# Sheet3.net
KiCad netlist of a schematic drawn in Altium Designer
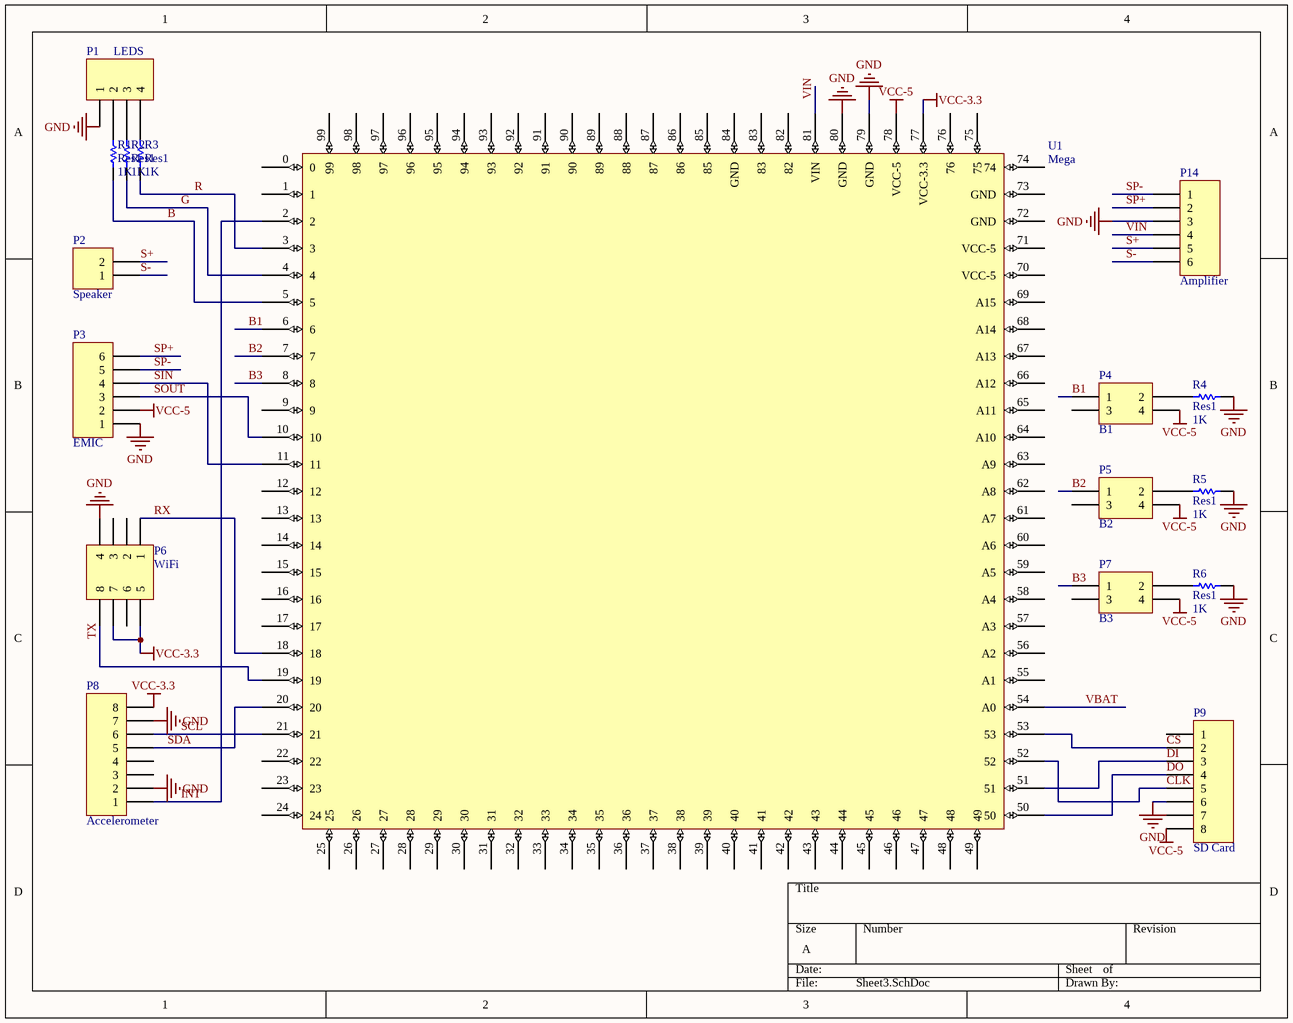
[diagram p0: Sheet3.SchDoc]

(export (version "E")
  (design (tool "Eeschema 10.0.6"))
  (components
    (comp (ref "P1")
      (value "LEDS")
      (footprint "HDR1X4")
      (description "Header, 4-Pin")
      (fields (field (name "PUBLISHER") "Altium Limited"))
      (libsource (lib "Miscellaneous Connectors") (part "Header 4"))
    )
    (comp (ref "P2")
      (value "Speaker")
      (footprint "HDR1X2")
      (description "Header, 2-Pin")
      (fields (field (name "PUBLISHER") "Altium Limited"))
      (libsource (lib "Miscellaneous Connectors") (part "Header 2"))
    )
    (comp (ref "P3")
      (value "EMIC")
      (footprint "EMIC")
      (description "Header, 6-Pin")
      (fields (field (name "PUBLISHER") "Altium Limited"))
      (libsource (lib "Miscellaneous Connectors") (part "Header 6"))
    )
    (comp (ref "P4")
      (value "B1")
      (footprint "HDR2X2")
      (description "Header, 2-Pin, Dual row")
      (fields (field (name "PUBLISHER") "Altium Limited"))
      (libsource (lib "Miscellaneous Connectors") (part "Header 2X2"))
    )
    (comp (ref "P5")
      (value "B2")
      (footprint "HDR2X2")
      (description "Header, 2-Pin, Dual row")
      (fields (field (name "PUBLISHER") "Altium Limited"))
      (libsource (lib "Miscellaneous Connectors") (part "Header 2X2"))
    )
    (comp (ref "P6")
      (value "WiFi")
      (footprint "WiFi")
      (description "Header, 4-Pin, Dual row")
      (fields (field (name "PUBLISHER") "Altium Limited"))
      (libsource (lib "Miscellaneous Connectors") (part "Header 4X2A"))
    )
    (comp (ref "P7")
      (value "B3")
      (footprint "HDR2X2")
      (description "Header, 2-Pin, Dual row")
      (fields (field (name "PUBLISHER") "Altium Limited"))
      (libsource (lib "Miscellaneous Connectors") (part "Header 2X2"))
    )
    (comp (ref "P8")
      (value "Accelerometer")
      (footprint "Acceelrometer")
      (description "Header, 8-Pin")
      (fields (field (name "PUBLISHER") "Altium Limited"))
      (libsource (lib "") (part "Header 8_1"))
    )
    (comp (ref "P9")
      (value "SD Card")
      (footprint "SD Card")
      (description "Header, 8-Pin")
      (fields (field (name "PUBLISHER") "Altium Limited"))
      (libsource (lib "Miscellaneous Connectors") (part "Header 8"))
    )
    (comp (ref "P14")
      (value "Amplifier")
      (footprint "HDR1X6")
      (description "Header, 6-Pin")
      (fields (field (name "PUBLISHER") "Altium Limited"))
      (libsource (lib "") (part "Header 6_1"))
    )
    (comp (ref "R1")
      (value "Res1")
      (footprint "14-1210")
      (description "Resistor")
      (fields (field (name "ALTIUM_VALUE") "1K") (field (name "PUBLISHER") "Altium Limited"))
      (libsource (lib "Miscellaneous Devices") (part "Res1"))
    )
    (comp (ref "R2")
      (value "Res1")
      (footprint "14-1210")
      (description "Resistor")
      (fields (field (name "ALTIUM_VALUE") "1K") (field (name "PUBLISHER") "Altium Limited"))
      (libsource (lib "Miscellaneous Devices") (part "Res1"))
    )
    (comp (ref "R3")
      (value "Res1")
      (footprint "14-1210")
      (description "Resistor")
      (fields (field (name "ALTIUM_VALUE") "1K") (field (name "PUBLISHER") "Altium Limited"))
      (libsource (lib "Miscellaneous Devices") (part "Res1"))
    )
    (comp (ref "R4")
      (value "Res1")
      (footprint "14-1210")
      (description "Resistor")
      (fields (field (name "ALTIUM_VALUE") "1K") (field (name "PUBLISHER") "Altium Limited"))
      (libsource (lib "Miscellaneous Devices") (part "Res1"))
    )
    (comp (ref "R5")
      (value "Res1")
      (footprint "14-1210")
      (description "Resistor")
      (fields (field (name "ALTIUM_VALUE") "1K") (field (name "PUBLISHER") "Altium Limited"))
      (libsource (lib "Miscellaneous Devices") (part "Res1"))
    )
    (comp (ref "R6")
      (value "Res1")
      (footprint "14-1210")
      (description "Resistor")
      (fields (field (name "ALTIUM_VALUE") "1K") (field (name "PUBLISHER") "Altium Limited"))
      (libsource (lib "Miscellaneous Devices") (part "Res1"))
    )
    (comp (ref "U1")
      (value "Mega")
      (footprint "Mega")
      (description "MEGA")
      (libsource (lib "Schlib1") (part "Mega"))
    )
  )
  (nets
    (net (code "1") (name "/B") (class "Default")
      (node (ref "R1") (pin "1") (pinfunction "1_1") (pintype "passive"))
      (node (ref "U1") (pin "5") (pinfunction "5_5") (pintype "bidirectional"))
    )
    (net (code "2") (name "/B1") (class "Default")
      (node (ref "P4") (pin "1") (pinfunction "1_1") (pintype "passive"))
      (node (ref "U1") (pin "6") (pinfunction "6_6") (pintype "bidirectional"))
    )
    (net (code "3") (name "/B2") (class "Default")
      (node (ref "P5") (pin "1") (pinfunction "1_1") (pintype "passive"))
      (node (ref "U1") (pin "7") (pinfunction "7_7") (pintype "bidirectional"))
    )
    (net (code "4") (name "/B3") (class "Default")
      (node (ref "P7") (pin "1") (pinfunction "1_1") (pintype "passive"))
      (node (ref "U1") (pin "8") (pinfunction "8_8") (pintype "bidirectional"))
    )
    (net (code "5") (name "/CLK") (class "Default")
      (node (ref "P9") (pin "5") (pinfunction "5_5") (pintype "passive"))
      (node (ref "U1") (pin "52") (pinfunction "52_52") (pintype "bidirectional"))
    )
    (net (code "6") (name "/CS") (class "Default")
      (node (ref "P9") (pin "2") (pinfunction "2_2") (pintype "passive"))
      (node (ref "U1") (pin "53") (pinfunction "53_53") (pintype "bidirectional"))
    )
    (net (code "7") (name "/DI") (class "Default")
      (node (ref "P9") (pin "3") (pinfunction "3_3") (pintype "passive"))
      (node (ref "U1") (pin "51") (pinfunction "51_51") (pintype "bidirectional"))
    )
    (net (code "8") (name "/DO") (class "Default")
      (node (ref "P9") (pin "4") (pinfunction "4_4") (pintype "passive"))
      (node (ref "U1") (pin "50") (pinfunction "50_50") (pintype "bidirectional"))
    )
    (net (code "9") (name "/G") (class "Default")
      (node (ref "R2") (pin "1") (pinfunction "1_1") (pintype "passive"))
      (node (ref "U1") (pin "4") (pinfunction "4_4") (pintype "bidirectional"))
    )
    (net (code "10") (name "/INT") (class "Default")
      (node (ref "P8") (pin "1") (pinfunction "1_1") (pintype "passive"))
      (node (ref "U1") (pin "2") (pinfunction "2_2") (pintype "bidirectional"))
    )
    (net (code "11") (name "/R") (class "Default")
      (node (ref "R3") (pin "1") (pinfunction "1_1") (pintype "passive"))
      (node (ref "U1") (pin "3") (pinfunction "3_3") (pintype "bidirectional"))
    )
    (net (code "12") (name "/RX") (class "Default")
      (node (ref "P6") (pin "1") (pinfunction "1_1") (pintype "passive"))
      (node (ref "U1") (pin "18") (pinfunction "18_18") (pintype "bidirectional"))
    )
    (net (code "13") (name "/S+") (class "Default")
      (node (ref "P14") (pin "5") (pinfunction "5_5") (pintype "passive"))
      (node (ref "P2") (pin "2") (pinfunction "2_2") (pintype "passive"))
    )
    (net (code "14") (name "/S-") (class "Default")
      (node (ref "P14") (pin "6") (pinfunction "6_6") (pintype "passive"))
      (node (ref "P2") (pin "1") (pinfunction "1_1") (pintype "passive"))
    )
    (net (code "15") (name "/SCL") (class "Default")
      (node (ref "P8") (pin "6") (pinfunction "6_6") (pintype "passive"))
      (node (ref "U1") (pin "21") (pinfunction "21_21") (pintype "bidirectional"))
    )
    (net (code "16") (name "/SDA") (class "Default")
      (node (ref "P8") (pin "5") (pinfunction "5_5") (pintype "passive"))
      (node (ref "U1") (pin "20") (pinfunction "20_20") (pintype "bidirectional"))
    )
    (net (code "17") (name "/SIN") (class "Default")
      (node (ref "P3") (pin "4") (pinfunction "4_4") (pintype "passive"))
      (node (ref "U1") (pin "11") (pinfunction "11_11") (pintype "bidirectional"))
    )
    (net (code "18") (name "/SOUT") (class "Default")
      (node (ref "P3") (pin "3") (pinfunction "3_3") (pintype "passive"))
      (node (ref "U1") (pin "10") (pinfunction "10_10") (pintype "bidirectional"))
    )
    (net (code "19") (name "/SP+") (class "Default")
      (node (ref "P14") (pin "2") (pinfunction "2_2") (pintype "passive"))
      (node (ref "P3") (pin "6") (pinfunction "6_6") (pintype "passive"))
    )
    (net (code "20") (name "/SP-") (class "Default")
      (node (ref "P14") (pin "1") (pinfunction "1_1") (pintype "passive"))
      (node (ref "P3") (pin "5") (pinfunction "5_5") (pintype "passive"))
    )
    (net (code "21") (name "/TX") (class "Default")
      (node (ref "P6") (pin "8") (pinfunction "8_8") (pintype "passive"))
      (node (ref "U1") (pin "19") (pinfunction "19_19") (pintype "bidirectional"))
    )
    (net (code "22") (name "/VBAT") (class "Default")
      (node (ref "U1") (pin "54") (pinfunction "A0_54") (pintype "bidirectional"))
    )
    (net (code "23") (name "/VIN") (class "Default")
      (node (ref "P14") (pin "4") (pinfunction "4_4") (pintype "passive"))
      (node (ref "U1") (pin "81") (pinfunction "VIN_81") (pintype "bidirectional"))
    )
    (net (code "24") (name "GND") (class "Default")
      (node (ref "P1") (pin "1") (pinfunction "1_1") (pintype "passive"))
      (node (ref "P14") (pin "3") (pinfunction "3_3") (pintype "passive"))
      (node (ref "P3") (pin "1") (pinfunction "1_1") (pintype "passive"))
      (node (ref "P6") (pin "4") (pinfunction "4_4") (pintype "passive"))
      (node (ref "P8") (pin "2") (pinfunction "2_2") (pintype "passive"))
      (node (ref "P8") (pin "7") (pinfunction "7_7") (pintype "passive"))
      (node (ref "P9") (pin "6") (pinfunction "6_6") (pintype "passive"))
      (node (ref "R4") (pin "2") (pinfunction "2_2") (pintype "passive"))
      (node (ref "R5") (pin "2") (pinfunction "2_2") (pintype "passive"))
      (node (ref "R6") (pin "2") (pinfunction "2_2") (pintype "passive"))
      (node (ref "U1") (pin "79") (pinfunction "GND_79") (pintype "bidirectional"))
      (node (ref "U1") (pin "80") (pinfunction "GND_80") (pintype "bidirectional"))
    )
    (net (code "25") (name "Net-(P1-Pad2)") (class "Default")
      (node (ref "P1") (pin "2") (pinfunction "2_2") (pintype "passive"))
      (node (ref "R1") (pin "2") (pinfunction "2_2") (pintype "passive"))
    )
    (net (code "26") (name "Net-(P1-Pad3)") (class "Default")
      (node (ref "P1") (pin "3") (pinfunction "3_3") (pintype "passive"))
      (node (ref "R2") (pin "2") (pinfunction "2_2") (pintype "passive"))
    )
    (net (code "27") (name "Net-(P1-Pad4)") (class "Default")
      (node (ref "P1") (pin "4") (pinfunction "4_4") (pintype "passive"))
      (node (ref "R3") (pin "2") (pinfunction "2_2") (pintype "passive"))
    )
    (net (code "28") (name "Net-(P4-Pad2)") (class "Default")
      (node (ref "P4") (pin "2") (pinfunction "2_2") (pintype "passive"))
      (node (ref "R4") (pin "1") (pinfunction "1_1") (pintype "passive"))
    )
    (net (code "29") (name "Net-(P5-Pad2)") (class "Default")
      (node (ref "P5") (pin "2") (pinfunction "2_2") (pintype "passive"))
      (node (ref "R5") (pin "1") (pinfunction "1_1") (pintype "passive"))
    )
    (net (code "30") (name "Net-(P7-Pad2)") (class "Default")
      (node (ref "P7") (pin "2") (pinfunction "2_2") (pintype "passive"))
      (node (ref "R6") (pin "1") (pinfunction "1_1") (pintype "passive"))
    )
    (net (code "31") (name "VCC-3.3") (class "Default")
      (node (ref "P6") (pin "5") (pinfunction "5_5") (pintype "passive"))
      (node (ref "P6") (pin "7") (pinfunction "7_7") (pintype "passive"))
      (node (ref "P8") (pin "8") (pinfunction "8_8") (pintype "passive"))
      (node (ref "U1") (pin "77") (pinfunction "VCC-3.3_77") (pintype "bidirectional"))
    )
    (net (code "32") (name "VCC-5") (class "Default")
      (node (ref "P3") (pin "2") (pinfunction "2_2") (pintype "passive"))
      (node (ref "P4") (pin "4") (pinfunction "4_4") (pintype "passive"))
      (node (ref "P5") (pin "4") (pinfunction "4_4") (pintype "passive"))
      (node (ref "P7") (pin "4") (pinfunction "4_4") (pintype "passive"))
      (node (ref "P9") (pin "8") (pinfunction "8_8") (pintype "passive"))
      (node (ref "U1") (pin "78") (pinfunction "VCC-5_78") (pintype "bidirectional"))
    )
    (net (code "33") (name "unconnected-(P4-Pad3)") (class "Default")
      (node (ref "P4") (pin "3") (pinfunction "3_3") (pintype "passive"))
    )
    (net (code "34") (name "unconnected-(P5-Pad3)") (class "Default")
      (node (ref "P5") (pin "3") (pinfunction "3_3") (pintype "passive"))
    )
    (net (code "35") (name "unconnected-(P6-Pad2)") (class "Default")
      (node (ref "P6") (pin "2") (pinfunction "2_2") (pintype "passive"))
    )
    (net (code "36") (name "unconnected-(P6-Pad3)") (class "Default")
      (node (ref "P6") (pin "3") (pinfunction "3_3") (pintype "passive"))
    )
    (net (code "37") (name "unconnected-(P6-Pad6)") (class "Default")
      (node (ref "P6") (pin "6") (pinfunction "6_6") (pintype "passive"))
    )
    (net (code "38") (name "unconnected-(P7-Pad3)") (class "Default")
      (node (ref "P7") (pin "3") (pinfunction "3_3") (pintype "passive"))
    )
    (net (code "39") (name "unconnected-(P8-Pad3)") (class "Default")
      (node (ref "P8") (pin "3") (pinfunction "3_3") (pintype "passive"))
    )
    (net (code "40") (name "unconnected-(P8-Pad4)") (class "Default")
      (node (ref "P8") (pin "4") (pinfunction "4_4") (pintype "passive"))
    )
    (net (code "41") (name "unconnected-(P9-Pad1)") (class "Default")
      (node (ref "P9") (pin "1") (pinfunction "1_1") (pintype "passive"))
    )
    (net (code "42") (name "unconnected-(P9-Pad7)") (class "Default")
      (node (ref "P9") (pin "7") (pinfunction "7_7") (pintype "passive"))
    )
    (net (code "43") (name "unconnected-(U1-A1-Pad55)") (class "Default")
      (node (ref "U1") (pin "55") (pinfunction "A1_55") (pintype "bidirectional"))
    )
    (net (code "44") (name "unconnected-(U1-A2-Pad56)") (class "Default")
      (node (ref "U1") (pin "56") (pinfunction "A2_56") (pintype "bidirectional"))
    )
    (net (code "45") (name "unconnected-(U1-A3-Pad57)") (class "Default")
      (node (ref "U1") (pin "57") (pinfunction "A3_57") (pintype "bidirectional"))
    )
    (net (code "46") (name "unconnected-(U1-A4-Pad58)") (class "Default")
      (node (ref "U1") (pin "58") (pinfunction "A4_58") (pintype "bidirectional"))
    )
    (net (code "47") (name "unconnected-(U1-A5-Pad59)") (class "Default")
      (node (ref "U1") (pin "59") (pinfunction "A5_59") (pintype "bidirectional"))
    )
    (net (code "48") (name "unconnected-(U1-A6-Pad60)") (class "Default")
      (node (ref "U1") (pin "60") (pinfunction "A6_60") (pintype "bidirectional"))
    )
    (net (code "49") (name "unconnected-(U1-A7-Pad61)") (class "Default")
      (node (ref "U1") (pin "61") (pinfunction "A7_61") (pintype "bidirectional"))
    )
    (net (code "50") (name "unconnected-(U1-A8-Pad62)") (class "Default")
      (node (ref "U1") (pin "62") (pinfunction "A8_62") (pintype "bidirectional"))
    )
    (net (code "51") (name "unconnected-(U1-A9-Pad63)") (class "Default")
      (node (ref "U1") (pin "63") (pinfunction "A9_63") (pintype "bidirectional"))
    )
    (net (code "52") (name "unconnected-(U1-A10-Pad64)") (class "Default")
      (node (ref "U1") (pin "64") (pinfunction "A10_64") (pintype "bidirectional"))
    )
    (net (code "53") (name "unconnected-(U1-A11-Pad65)") (class "Default")
      (node (ref "U1") (pin "65") (pinfunction "A11_65") (pintype "bidirectional"))
    )
    (net (code "54") (name "unconnected-(U1-A12-Pad66)") (class "Default")
      (node (ref "U1") (pin "66") (pinfunction "A12_66") (pintype "bidirectional"))
    )
    (net (code "55") (name "unconnected-(U1-A13-Pad67)") (class "Default")
      (node (ref "U1") (pin "67") (pinfunction "A13_67") (pintype "bidirectional"))
    )
    (net (code "56") (name "unconnected-(U1-A14-Pad68)") (class "Default")
      (node (ref "U1") (pin "68") (pinfunction "A14_68") (pintype "bidirectional"))
    )
    (net (code "57") (name "unconnected-(U1-A15-Pad69)") (class "Default")
      (node (ref "U1") (pin "69") (pinfunction "A15_69") (pintype "bidirectional"))
    )
    (net (code "58") (name "unconnected-(U1-GND-Pad72)") (class "Default")
      (node (ref "U1") (pin "72") (pinfunction "GND_72") (pintype "bidirectional"))
    )
    (net (code "59") (name "unconnected-(U1-GND-Pad73)") (class "Default")
      (node (ref "U1") (pin "73") (pinfunction "GND_73") (pintype "bidirectional"))
    )
    (net (code "60") (name "unconnected-(U1-GND-Pad84)") (class "Default")
      (node (ref "U1") (pin "84") (pinfunction "GND_84") (pintype "bidirectional"))
    )
    (net (code "61") (name "unconnected-(U1-Pad0)") (class "Default")
      (node (ref "U1") (pin "0") (pinfunction "0_0") (pintype "bidirectional"))
    )
    (net (code "62") (name "unconnected-(U1-Pad1)") (class "Default")
      (node (ref "U1") (pin "1") (pinfunction "1_1") (pintype "bidirectional"))
    )
    (net (code "63") (name "unconnected-(U1-Pad9)") (class "Default")
      (node (ref "U1") (pin "9") (pinfunction "9_9") (pintype "bidirectional"))
    )
    (net (code "64") (name "unconnected-(U1-Pad12)") (class "Default")
      (node (ref "U1") (pin "12") (pinfunction "12_12") (pintype "bidirectional"))
    )
    (net (code "65") (name "unconnected-(U1-Pad13)") (class "Default")
      (node (ref "U1") (pin "13") (pinfunction "13_13") (pintype "bidirectional"))
    )
    (net (code "66") (name "unconnected-(U1-Pad14)") (class "Default")
      (node (ref "U1") (pin "14") (pinfunction "14_14") (pintype "bidirectional"))
    )
    (net (code "67") (name "unconnected-(U1-Pad15)") (class "Default")
      (node (ref "U1") (pin "15") (pinfunction "15_15") (pintype "bidirectional"))
    )
    (net (code "68") (name "unconnected-(U1-Pad16)") (class "Default")
      (node (ref "U1") (pin "16") (pinfunction "16_16") (pintype "bidirectional"))
    )
    (net (code "69") (name "unconnected-(U1-Pad17)") (class "Default")
      (node (ref "U1") (pin "17") (pinfunction "17_17") (pintype "bidirectional"))
    )
    (net (code "70") (name "unconnected-(U1-Pad22)") (class "Default")
      (node (ref "U1") (pin "22") (pinfunction "22_22") (pintype "bidirectional"))
    )
    (net (code "71") (name "unconnected-(U1-Pad23)") (class "Default")
      (node (ref "U1") (pin "23") (pinfunction "23_23") (pintype "bidirectional"))
    )
    (net (code "72") (name "unconnected-(U1-Pad24)") (class "Default")
      (node (ref "U1") (pin "24") (pinfunction "24_24") (pintype "bidirectional"))
    )
    (net (code "73") (name "unconnected-(U1-Pad25)") (class "Default")
      (node (ref "U1") (pin "25") (pinfunction "25_25") (pintype "bidirectional"))
    )
    (net (code "74") (name "unconnected-(U1-Pad26)") (class "Default")
      (node (ref "U1") (pin "26") (pinfunction "26_26") (pintype "bidirectional"))
    )
    (net (code "75") (name "unconnected-(U1-Pad27)") (class "Default")
      (node (ref "U1") (pin "27") (pinfunction "27_27") (pintype "bidirectional"))
    )
    (net (code "76") (name "unconnected-(U1-Pad28)") (class "Default")
      (node (ref "U1") (pin "28") (pinfunction "28_28") (pintype "bidirectional"))
    )
    (net (code "77") (name "unconnected-(U1-Pad29)") (class "Default")
      (node (ref "U1") (pin "29") (pinfunction "29_29") (pintype "bidirectional"))
    )
    (net (code "78") (name "unconnected-(U1-Pad30)") (class "Default")
      (node (ref "U1") (pin "30") (pinfunction "30_30") (pintype "bidirectional"))
    )
    (net (code "79") (name "unconnected-(U1-Pad31)") (class "Default")
      (node (ref "U1") (pin "31") (pinfunction "31_31") (pintype "bidirectional"))
    )
    (net (code "80") (name "unconnected-(U1-Pad32)") (class "Default")
      (node (ref "U1") (pin "32") (pinfunction "32_32") (pintype "bidirectional"))
    )
    (net (code "81") (name "unconnected-(U1-Pad33)") (class "Default")
      (node (ref "U1") (pin "33") (pinfunction "33_33") (pintype "bidirectional"))
    )
    (net (code "82") (name "unconnected-(U1-Pad34)") (class "Default")
      (node (ref "U1") (pin "34") (pinfunction "34_34") (pintype "bidirectional"))
    )
    (net (code "83") (name "unconnected-(U1-Pad35)") (class "Default")
      (node (ref "U1") (pin "35") (pinfunction "35_35") (pintype "bidirectional"))
    )
    (net (code "84") (name "unconnected-(U1-Pad36)") (class "Default")
      (node (ref "U1") (pin "36") (pinfunction "36_36") (pintype "bidirectional"))
    )
    (net (code "85") (name "unconnected-(U1-Pad37)") (class "Default")
      (node (ref "U1") (pin "37") (pinfunction "37_37") (pintype "bidirectional"))
    )
    (net (code "86") (name "unconnected-(U1-Pad38)") (class "Default")
      (node (ref "U1") (pin "38") (pinfunction "38_38") (pintype "bidirectional"))
    )
    (net (code "87") (name "unconnected-(U1-Pad39)") (class "Default")
      (node (ref "U1") (pin "39") (pinfunction "39_39") (pintype "bidirectional"))
    )
    (net (code "88") (name "unconnected-(U1-Pad40)") (class "Default")
      (node (ref "U1") (pin "40") (pinfunction "40_40") (pintype "bidirectional"))
    )
    (net (code "89") (name "unconnected-(U1-Pad41)") (class "Default")
      (node (ref "U1") (pin "41") (pinfunction "41_41") (pintype "bidirectional"))
    )
    (net (code "90") (name "unconnected-(U1-Pad42)") (class "Default")
      (node (ref "U1") (pin "42") (pinfunction "42_42") (pintype "bidirectional"))
    )
    (net (code "91") (name "unconnected-(U1-Pad43)") (class "Default")
      (node (ref "U1") (pin "43") (pinfunction "43_43") (pintype "bidirectional"))
    )
    (net (code "92") (name "unconnected-(U1-Pad44)") (class "Default")
      (node (ref "U1") (pin "44") (pinfunction "44_44") (pintype "bidirectional"))
    )
    (net (code "93") (name "unconnected-(U1-Pad45)") (class "Default")
      (node (ref "U1") (pin "45") (pinfunction "45_45") (pintype "bidirectional"))
    )
    (net (code "94") (name "unconnected-(U1-Pad46)") (class "Default")
      (node (ref "U1") (pin "46") (pinfunction "46_46") (pintype "bidirectional"))
    )
    (net (code "95") (name "unconnected-(U1-Pad47)") (class "Default")
      (node (ref "U1") (pin "47") (pinfunction "47_47") (pintype "bidirectional"))
    )
    (net (code "96") (name "unconnected-(U1-Pad48)") (class "Default")
      (node (ref "U1") (pin "48") (pinfunction "48_48") (pintype "bidirectional"))
    )
    (net (code "97") (name "unconnected-(U1-Pad49)") (class "Default")
      (node (ref "U1") (pin "49") (pinfunction "49_49") (pintype "bidirectional"))
    )
    (net (code "98") (name "unconnected-(U1-Pad74)") (class "Default")
      (node (ref "U1") (pin "74") (pinfunction "74_74") (pintype "bidirectional"))
    )
    (net (code "99") (name "unconnected-(U1-Pad75)") (class "Default")
      (node (ref "U1") (pin "75") (pinfunction "75_75") (pintype "bidirectional"))
    )
    (net (code "100") (name "unconnected-(U1-Pad76)") (class "Default")
      (node (ref "U1") (pin "76") (pinfunction "76_76") (pintype "bidirectional"))
    )
    (net (code "101") (name "unconnected-(U1-Pad82)") (class "Default")
      (node (ref "U1") (pin "82") (pinfunction "82_82") (pintype "bidirectional"))
    )
    (net (code "102") (name "unconnected-(U1-Pad83)") (class "Default")
      (node (ref "U1") (pin "83") (pinfunction "83_83") (pintype "bidirectional"))
    )
    (net (code "103") (name "unconnected-(U1-Pad85)") (class "Default")
      (node (ref "U1") (pin "85") (pinfunction "85_85") (pintype "bidirectional"))
    )
    (net (code "104") (name "unconnected-(U1-Pad86)") (class "Default")
      (node (ref "U1") (pin "86") (pinfunction "86_86") (pintype "bidirectional"))
    )
    (net (code "105") (name "unconnected-(U1-Pad87)") (class "Default")
      (node (ref "U1") (pin "87") (pinfunction "87_87") (pintype "bidirectional"))
    )
    (net (code "106") (name "unconnected-(U1-Pad88)") (class "Default")
      (node (ref "U1") (pin "88") (pinfunction "88_88") (pintype "bidirectional"))
    )
    (net (code "107") (name "unconnected-(U1-Pad89)") (class "Default")
      (node (ref "U1") (pin "89") (pinfunction "89_89") (pintype "bidirectional"))
    )
    (net (code "108") (name "unconnected-(U1-Pad90)") (class "Default")
      (node (ref "U1") (pin "90") (pinfunction "90_90") (pintype "bidirectional"))
    )
    (net (code "109") (name "unconnected-(U1-Pad91)") (class "Default")
      (node (ref "U1") (pin "91") (pinfunction "91_91") (pintype "bidirectional"))
    )
    (net (code "110") (name "unconnected-(U1-Pad92)") (class "Default")
      (node (ref "U1") (pin "92") (pinfunction "92_92") (pintype "bidirectional"))
    )
    (net (code "111") (name "unconnected-(U1-Pad93)") (class "Default")
      (node (ref "U1") (pin "93") (pinfunction "93_93") (pintype "bidirectional"))
    )
    (net (code "112") (name "unconnected-(U1-Pad94)") (class "Default")
      (node (ref "U1") (pin "94") (pinfunction "94_94") (pintype "bidirectional"))
    )
    (net (code "113") (name "unconnected-(U1-Pad95)") (class "Default")
      (node (ref "U1") (pin "95") (pinfunction "95_95") (pintype "bidirectional"))
    )
    (net (code "114") (name "unconnected-(U1-Pad96)") (class "Default")
      (node (ref "U1") (pin "96") (pinfunction "96_96") (pintype "bidirectional"))
    )
    (net (code "115") (name "unconnected-(U1-Pad97)") (class "Default")
      (node (ref "U1") (pin "97") (pinfunction "97_97") (pintype "bidirectional"))
    )
    (net (code "116") (name "unconnected-(U1-Pad98)") (class "Default")
      (node (ref "U1") (pin "98") (pinfunction "98_98") (pintype "bidirectional"))
    )
    (net (code "117") (name "unconnected-(U1-Pad99)") (class "Default")
      (node (ref "U1") (pin "99") (pinfunction "99_99") (pintype "bidirectional"))
    )
    (net (code "118") (name "unconnected-(U1-VCC-5-Pad70)") (class "Default")
      (node (ref "U1") (pin "70") (pinfunction "VCC-5_70") (pintype "bidirectional"))
    )
    (net (code "119") (name "unconnected-(U1-VCC-5-Pad71)") (class "Default")
      (node (ref "U1") (pin "71") (pinfunction "VCC-5_71") (pintype "bidirectional"))
    )
  )
)
